# Sh_Output.net
KiCad netlist of a schematic drawn in Altium Designer
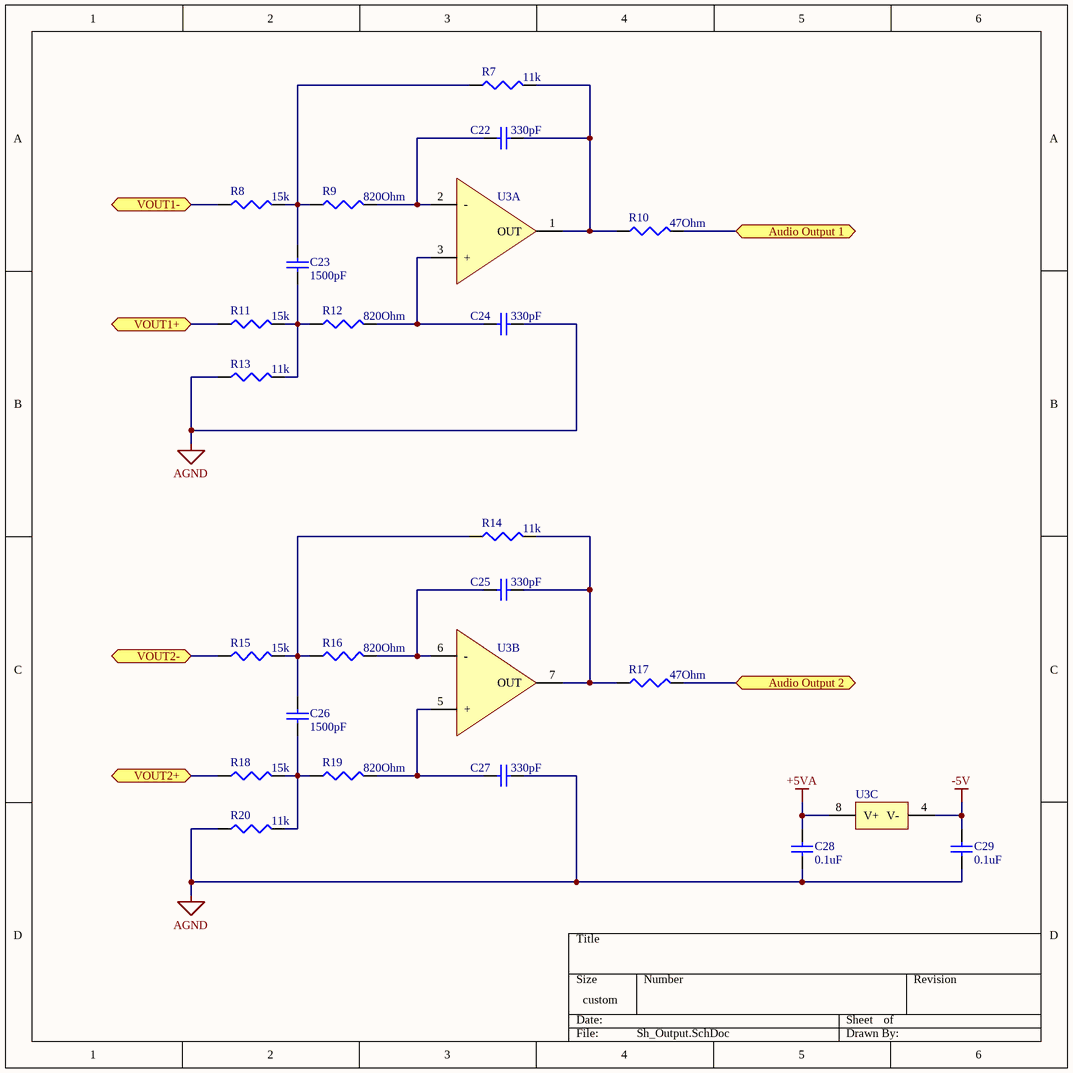
[diagram p0: Sh_Output.SchDoc]

(export (version "E")
  (design (tool "Eeschema 10.0.6"))
  (components
    (comp (ref "C22")
      (value "330pF")
      (footprint "1608[0603]")
      (description "Capacitor (Semiconductor SIM Model)")
      (fields (field (name "Comment") "Cap Semi") (field (name "PUBLISHER") "Altium Limited"))
      (libsource (lib "Miscellaneous Devices") (part "Cap Semi"))
    )
    (comp (ref "C23")
      (value "1500pF")
      (footprint "1608[0603]")
      (description "Capacitor (Semiconductor SIM Model)")
      (fields (field (name "Comment") "Cap Semi") (field (name "PUBLISHER") "Altium Limited"))
      (libsource (lib "Miscellaneous Devices") (part "Cap Semi"))
    )
    (comp (ref "C24")
      (value "330pF")
      (footprint "1608[0603]")
      (description "Capacitor (Semiconductor SIM Model)")
      (fields (field (name "Comment") "Cap Semi") (field (name "PUBLISHER") "Altium Limited"))
      (libsource (lib "Miscellaneous Devices") (part "Cap Semi"))
    )
    (comp (ref "C25")
      (value "330pF")
      (footprint "1608[0603]")
      (description "Capacitor (Semiconductor SIM Model)")
      (fields (field (name "Comment") "Cap Semi") (field (name "PUBLISHER") "Altium Limited"))
      (libsource (lib "Miscellaneous Devices") (part "Cap Semi"))
    )
    (comp (ref "C26")
      (value "1500pF")
      (footprint "1608[0603]")
      (description "Capacitor (Semiconductor SIM Model)")
      (fields (field (name "Comment") "Cap Semi") (field (name "PUBLISHER") "Altium Limited"))
      (libsource (lib "Miscellaneous Devices") (part "Cap Semi"))
    )
    (comp (ref "C27")
      (value "330pF")
      (footprint "1608[0603]")
      (description "Capacitor (Semiconductor SIM Model)")
      (fields (field (name "Comment") "Cap Semi") (field (name "PUBLISHER") "Altium Limited"))
      (libsource (lib "Miscellaneous Devices") (part "Cap Semi"))
    )
    (comp (ref "C28")
      (value "0.1uF")
      (footprint "1608[0603]")
      (description "Capacitor (Semiconductor SIM Model)")
      (fields (field (name "Comment") "Cap Semi") (field (name "PUBLISHER") "Altium Limited"))
      (libsource (lib "Miscellaneous Devices") (part "Cap Semi"))
    )
    (comp (ref "C29")
      (value "0.1uF")
      (footprint "1608[0603]")
      (description "Capacitor (Semiconductor SIM Model)")
      (fields (field (name "Comment") "Cap Semi") (field (name "PUBLISHER") "Altium Limited"))
      (libsource (lib "Miscellaneous Devices") (part "Cap Semi"))
    )
    (comp (ref "R7")
      (value "11k")
      (footprint "J1-0603")
      (description "Resistor")
      (fields (field (name "Comment") "Res3") (field (name "PUBLISHER") "Altium Limited"))
      (libsource (lib "Miscellaneous Devices") (part "Res3"))
    )
    (comp (ref "R8")
      (value "15k")
      (footprint "J1-0603")
      (description "Resistor")
      (fields (field (name "Comment") "Res3") (field (name "PUBLISHER") "Altium Limited"))
      (libsource (lib "Miscellaneous Devices") (part "Res3"))
    )
    (comp (ref "R9")
      (value "820Ohm")
      (footprint "J1-0603")
      (description "Resistor")
      (fields (field (name "Comment") "Res3") (field (name "PUBLISHER") "Altium Limited"))
      (libsource (lib "Miscellaneous Devices") (part "Res3"))
    )
    (comp (ref "R10")
      (value "47Ohm")
      (footprint "J1-0603")
      (description "Resistor")
      (fields (field (name "Comment") "Res3") (field (name "PUBLISHER") "Altium Limited"))
      (libsource (lib "Miscellaneous Devices") (part "Res3"))
    )
    (comp (ref "R11")
      (value "15k")
      (footprint "J1-0603")
      (description "Resistor")
      (fields (field (name "Comment") "Res3") (field (name "PUBLISHER") "Altium Limited"))
      (libsource (lib "Miscellaneous Devices") (part "Res3"))
    )
    (comp (ref "R12")
      (value "820Ohm")
      (footprint "J1-0603")
      (description "Resistor")
      (fields (field (name "Comment") "Res3") (field (name "PUBLISHER") "Altium Limited"))
      (libsource (lib "Miscellaneous Devices") (part "Res3"))
    )
    (comp (ref "R13")
      (value "11k")
      (footprint "J1-0603")
      (description "Resistor")
      (fields (field (name "Comment") "Res3") (field (name "PUBLISHER") "Altium Limited"))
      (libsource (lib "Miscellaneous Devices") (part "Res3"))
    )
    (comp (ref "R14")
      (value "11k")
      (footprint "J1-0603")
      (description "Resistor")
      (fields (field (name "Comment") "Res3") (field (name "PUBLISHER") "Altium Limited"))
      (libsource (lib "Miscellaneous Devices") (part "Res3"))
    )
    (comp (ref "R15")
      (value "15k")
      (footprint "J1-0603")
      (description "Resistor")
      (fields (field (name "Comment") "Res3") (field (name "PUBLISHER") "Altium Limited"))
      (libsource (lib "Miscellaneous Devices") (part "Res3"))
    )
    (comp (ref "R16")
      (value "820Ohm")
      (footprint "J1-0603")
      (description "Resistor")
      (fields (field (name "Comment") "Res3") (field (name "PUBLISHER") "Altium Limited"))
      (libsource (lib "Miscellaneous Devices") (part "Res3"))
    )
    (comp (ref "R17")
      (value "47Ohm")
      (footprint "J1-0603")
      (description "Resistor")
      (fields (field (name "Comment") "Res3") (field (name "PUBLISHER") "Altium Limited"))
      (libsource (lib "Miscellaneous Devices") (part "Res3"))
    )
    (comp (ref "R18")
      (value "15k")
      (footprint "J1-0603")
      (description "Resistor")
      (fields (field (name "Comment") "Res3") (field (name "PUBLISHER") "Altium Limited"))
      (libsource (lib "Miscellaneous Devices") (part "Res3"))
    )
    (comp (ref "R19")
      (value "820Ohm")
      (footprint "J1-0603")
      (description "Resistor")
      (fields (field (name "Comment") "Res3") (field (name "PUBLISHER") "Altium Limited"))
      (libsource (lib "Miscellaneous Devices") (part "Res3"))
    )
    (comp (ref "R20")
      (value "11k")
      (footprint "J1-0603")
      (description "Resistor")
      (fields (field (name "Comment") "Res3") (field (name "PUBLISHER") "Altium Limited"))
      (libsource (lib "Miscellaneous Devices") (part "Res3"))
    )
    (comp (ref "U3")
      (value "NE5532A")
      (footprint "SOIC127P600-8AL")
      (description "Amplificateur Opérationnel")
      (libsource (lib "Bonjour") (part "Ampli_op"))
    )
  )
  (nets
    (net (code "1") (name "+5VA") (class "Default")
      (node (ref "C28") (pin "1") (pinfunction "1_1") (pintype "passive"))
      (node (ref "U3") (pin "8") (pinfunction "V+_8") (pintype "passive"))
    )
    (net (code "2") (name "-5V") (class "Default")
      (node (ref "C29") (pin "1") (pinfunction "1_1") (pintype "passive"))
      (node (ref "U3") (pin "4") (pinfunction "V-_4") (pintype "passive"))
    )
    (net (code "3") (name "/Audio Output 1") (class "Default")
      (node (ref "R10") (pin "2") (pinfunction "2_2") (pintype "passive"))
    )
    (net (code "4") (name "/Audio Output 2") (class "Default")
      (node (ref "R17") (pin "2") (pinfunction "2_2") (pintype "passive"))
    )
    (net (code "5") (name "/VOUT1+") (class "Default")
      (node (ref "R11") (pin "1") (pinfunction "1_1") (pintype "passive"))
    )
    (net (code "6") (name "/VOUT1-") (class "Default")
      (node (ref "R8") (pin "1") (pinfunction "1_1") (pintype "passive"))
    )
    (net (code "7") (name "/VOUT2+") (class "Default")
      (node (ref "R18") (pin "1") (pinfunction "1_1") (pintype "passive"))
    )
    (net (code "8") (name "/VOUT2-") (class "Default")
      (node (ref "R15") (pin "1") (pinfunction "1_1") (pintype "passive"))
    )
    (net (code "9") (name "AGND") (class "Default")
      (node (ref "C24") (pin "1") (pinfunction "1_1") (pintype "passive"))
      (node (ref "C27") (pin "1") (pinfunction "1_1") (pintype "passive"))
      (node (ref "C28") (pin "2") (pinfunction "2_2") (pintype "passive"))
      (node (ref "C29") (pin "2") (pinfunction "2_2") (pintype "passive"))
      (node (ref "R13") (pin "1") (pinfunction "1_1") (pintype "passive"))
      (node (ref "R20") (pin "1") (pinfunction "1_1") (pintype "passive"))
    )
    (net (code "10") (name "Net-(C23-Pad1)") (class "Default")
      (node (ref "C23") (pin "1") (pinfunction "1_1") (pintype "passive"))
      (node (ref "R7") (pin "1") (pinfunction "1_1") (pintype "passive"))
      (node (ref "R8") (pin "2") (pinfunction "2_2") (pintype "passive"))
      (node (ref "R9") (pin "1") (pinfunction "1_1") (pintype "passive"))
    )
    (net (code "11") (name "Net-(C23-Pad2)") (class "Default")
      (node (ref "C23") (pin "2") (pinfunction "2_2") (pintype "passive"))
      (node (ref "R11") (pin "2") (pinfunction "2_2") (pintype "passive"))
      (node (ref "R12") (pin "1") (pinfunction "1_1") (pintype "passive"))
      (node (ref "R13") (pin "2") (pinfunction "2_2") (pintype "passive"))
    )
    (net (code "12") (name "Net-(C26-Pad1)") (class "Default")
      (node (ref "C26") (pin "1") (pinfunction "1_1") (pintype "passive"))
      (node (ref "R14") (pin "1") (pinfunction "1_1") (pintype "passive"))
      (node (ref "R15") (pin "2") (pinfunction "2_2") (pintype "passive"))
      (node (ref "R16") (pin "1") (pinfunction "1_1") (pintype "passive"))
    )
    (net (code "13") (name "Net-(C26-Pad2)") (class "Default")
      (node (ref "C26") (pin "2") (pinfunction "2_2") (pintype "passive"))
      (node (ref "R18") (pin "2") (pinfunction "2_2") (pintype "passive"))
      (node (ref "R19") (pin "1") (pinfunction "1_1") (pintype "passive"))
      (node (ref "R20") (pin "2") (pinfunction "2_2") (pintype "passive"))
    )
    (net (code "14") (name "Net-(U3A-+)") (class "Default")
      (node (ref "C24") (pin "2") (pinfunction "2_2") (pintype "passive"))
      (node (ref "R12") (pin "2") (pinfunction "2_2") (pintype "passive"))
      (node (ref "U3") (pin "3") (pinfunction "+_3") (pintype "passive"))
    )
    (net (code "15") (name "Net-(U3A--)") (class "Default")
      (node (ref "C22") (pin "2") (pinfunction "2_2") (pintype "passive"))
      (node (ref "R9") (pin "2") (pinfunction "2_2") (pintype "passive"))
      (node (ref "U3") (pin "2") (pinfunction "-_2") (pintype "passive"))
    )
    (net (code "16") (name "Net-(U3A-OUT)") (class "Default")
      (node (ref "C22") (pin "1") (pinfunction "1_1") (pintype "passive"))
      (node (ref "R10") (pin "1") (pinfunction "1_1") (pintype "passive"))
      (node (ref "R7") (pin "2") (pinfunction "2_2") (pintype "passive"))
      (node (ref "U3") (pin "1") (pinfunction "OUT_1") (pintype "passive"))
    )
    (net (code "17") (name "Net-(U3B-+)") (class "Default")
      (node (ref "C27") (pin "2") (pinfunction "2_2") (pintype "passive"))
      (node (ref "R19") (pin "2") (pinfunction "2_2") (pintype "passive"))
      (node (ref "U3") (pin "5") (pinfunction "+_5") (pintype "passive"))
    )
    (net (code "18") (name "Net-(U3B--)") (class "Default")
      (node (ref "C25") (pin "2") (pinfunction "2_2") (pintype "passive"))
      (node (ref "R16") (pin "2") (pinfunction "2_2") (pintype "passive"))
      (node (ref "U3") (pin "6") (pinfunction "-_6") (pintype "passive"))
    )
    (net (code "19") (name "Net-(U3B-OUT)") (class "Default")
      (node (ref "C25") (pin "1") (pinfunction "1_1") (pintype "passive"))
      (node (ref "R14") (pin "2") (pinfunction "2_2") (pintype "passive"))
      (node (ref "R17") (pin "1") (pinfunction "1_1") (pintype "passive"))
      (node (ref "U3") (pin "7") (pinfunction "OUT_7") (pintype "passive"))
    )
  )
)
